# PCA9685.net
KiCad netlist of a schematic drawn in Altium Designer
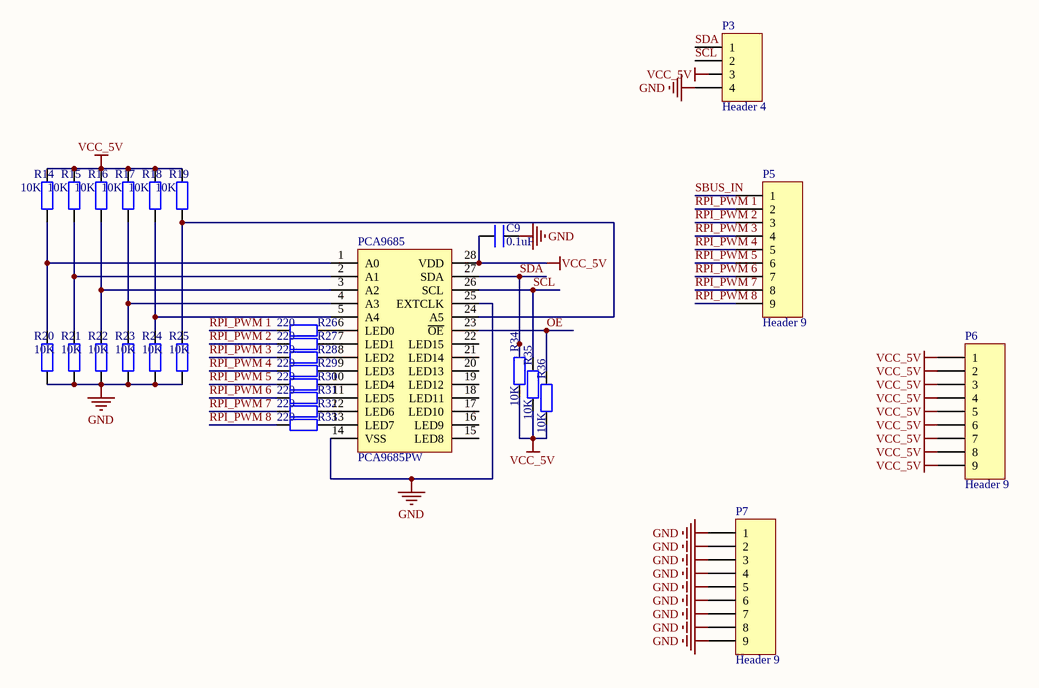
[diagram p0: PCA9685.SchDoc]

(export (version "E")
  (design (tool "Eeschema 10.0.6"))
  (components
    (comp (ref "C9") (value "0.1uF") (footprint "0805") (libsource (lib "OLED模块封装库") (part "C")))
    (comp (ref "P3")
      (value "Header 4")
      (footprint "HDR1X4")
      (description "Header, 4-Pin")
      (fields (field (name "PUBLISHER") "Altium Limited"))
      (libsource (lib "Miscellaneous Connectors") (part "Header 4"))
    )
    (comp (ref "P5")
      (value "Header 9")
      (footprint "HDR1X9")
      (description "Header, 9-Pin")
      (fields (field (name "PUBLISHER") "Altium Limited"))
      (libsource (lib "Miscellaneous Connectors") (part "Header 9"))
    )
    (comp (ref "P6")
      (value "Header 9")
      (footprint "HDR1X9")
      (description "Header, 9-Pin")
      (fields (field (name "PUBLISHER") "Altium Limited"))
      (libsource (lib "Miscellaneous Connectors") (part "Header 9"))
    )
    (comp (ref "P7")
      (value "Header 9")
      (footprint "HDR1X9")
      (description "Header, 9-Pin")
      (fields (field (name "PUBLISHER") "Altium Limited"))
      (libsource (lib "Miscellaneous Connectors") (part "Header 9"))
    )
    (comp (ref "PCA9685")
      (value "PCA9685PW")
      (footprint "PCA9685PW")
      (libsource (lib "Integrated_PCA 9685") (part "PCA9685PW"))
    )
    (comp (ref "R14")
      (value "10K")
      (footprint "3.5TFTLCD封装库:0805")
      (description "Resistor")
      (fields (field (name "Comment") "Res2") (field (name "PUBLISHER") "Altium Limited"))
      (libsource (lib "") (part "Res2_1"))
    )
    (comp (ref "R15")
      (value "10K")
      (footprint "3.5TFTLCD封装库:0805")
      (description "Resistor")
      (fields (field (name "Comment") "Res2") (field (name "PUBLISHER") "Altium Limited"))
      (libsource (lib "") (part "Res2_1"))
    )
    (comp (ref "R16")
      (value "10K")
      (footprint "3.5TFTLCD封装库:0805")
      (description "Resistor")
      (fields (field (name "Comment") "Res2") (field (name "PUBLISHER") "Altium Limited"))
      (libsource (lib "") (part "Res2_1"))
    )
    (comp (ref "R17")
      (value "10K")
      (footprint "3.5TFTLCD封装库:0805")
      (description "Resistor")
      (fields (field (name "Comment") "Res2") (field (name "PUBLISHER") "Altium Limited"))
      (libsource (lib "") (part "Res2_1"))
    )
    (comp (ref "R18")
      (value "10K")
      (footprint "3.5TFTLCD封装库:0805")
      (description "Resistor")
      (fields (field (name "Comment") "Res2") (field (name "PUBLISHER") "Altium Limited"))
      (libsource (lib "") (part "Res2_1"))
    )
    (comp (ref "R19")
      (value "10K")
      (footprint "3.5TFTLCD封装库:0805")
      (description "Resistor")
      (fields (field (name "Comment") "Res2") (field (name "PUBLISHER") "Altium Limited"))
      (libsource (lib "") (part "Res2_1"))
    )
    (comp (ref "R20")
      (value "10K")
      (footprint "3.5TFTLCD封装库:0805")
      (description "Resistor")
      (fields (field (name "Comment") "Res2") (field (name "PUBLISHER") "Altium Limited"))
      (libsource (lib "") (part "Res2_1"))
    )
    (comp (ref "R21")
      (value "10K")
      (footprint "3.5TFTLCD封装库:0805")
      (description "Resistor")
      (fields (field (name "Comment") "Res2") (field (name "PUBLISHER") "Altium Limited"))
      (libsource (lib "") (part "Res2_1"))
    )
    (comp (ref "R22")
      (value "10K")
      (footprint "3.5TFTLCD封装库:0805")
      (description "Resistor")
      (fields (field (name "Comment") "Res2") (field (name "PUBLISHER") "Altium Limited"))
      (libsource (lib "") (part "Res2_1"))
    )
    (comp (ref "R23")
      (value "10K")
      (footprint "3.5TFTLCD封装库:0805")
      (description "Resistor")
      (fields (field (name "Comment") "Res2") (field (name "PUBLISHER") "Altium Limited"))
      (libsource (lib "") (part "Res2_1"))
    )
    (comp (ref "R24")
      (value "10K")
      (footprint "3.5TFTLCD封装库:0805")
      (description "Resistor")
      (fields (field (name "Comment") "Res2") (field (name "PUBLISHER") "Altium Limited"))
      (libsource (lib "") (part "Res2_1"))
    )
    (comp (ref "R25")
      (value "10K")
      (footprint "3.5TFTLCD封装库:0805")
      (description "Resistor")
      (fields (field (name "Comment") "Res2") (field (name "PUBLISHER") "Altium Limited"))
      (libsource (lib "") (part "Res2_1"))
    )
    (comp (ref "R26")
      (value "220")
      (footprint "3.5TFTLCD封装库:0805")
      (description "Resistor")
      (fields (field (name "Comment") "Res2") (field (name "PUBLISHER") "Altium Limited"))
      (libsource (lib "Miscellaneous Devices") (part "Res2"))
    )
    (comp (ref "R27")
      (value "220")
      (footprint "3.5TFTLCD封装库:0805")
      (description "Resistor")
      (fields (field (name "Comment") "Res2") (field (name "PUBLISHER") "Altium Limited"))
      (libsource (lib "Miscellaneous Devices") (part "Res2"))
    )
    (comp (ref "R28")
      (value "220")
      (footprint "3.5TFTLCD封装库:0805")
      (description "Resistor")
      (fields (field (name "Comment") "Res2") (field (name "PUBLISHER") "Altium Limited"))
      (libsource (lib "Miscellaneous Devices") (part "Res2"))
    )
    (comp (ref "R29")
      (value "220")
      (footprint "3.5TFTLCD封装库:0805")
      (description "Resistor")
      (fields (field (name "Comment") "Res2") (field (name "PUBLISHER") "Altium Limited"))
      (libsource (lib "Miscellaneous Devices") (part "Res2"))
    )
    (comp (ref "R30")
      (value "220")
      (footprint "3.5TFTLCD封装库:0805")
      (description "Resistor")
      (fields (field (name "Comment") "Res2") (field (name "PUBLISHER") "Altium Limited"))
      (libsource (lib "Miscellaneous Devices") (part "Res2"))
    )
    (comp (ref "R31")
      (value "220")
      (footprint "3.5TFTLCD封装库:0805")
      (description "Resistor")
      (fields (field (name "Comment") "Res2") (field (name "PUBLISHER") "Altium Limited"))
      (libsource (lib "Miscellaneous Devices") (part "Res2"))
    )
    (comp (ref "R32")
      (value "220")
      (footprint "3.5TFTLCD封装库:0805")
      (description "Resistor")
      (fields (field (name "Comment") "Res2") (field (name "PUBLISHER") "Altium Limited"))
      (libsource (lib "Miscellaneous Devices") (part "Res2"))
    )
    (comp (ref "R33")
      (value "220")
      (footprint "3.5TFTLCD封装库:0805")
      (description "Resistor")
      (fields (field (name "Comment") "Res2") (field (name "PUBLISHER") "Altium Limited"))
      (libsource (lib "Miscellaneous Devices") (part "Res2"))
    )
    (comp (ref "R34")
      (value "10K")
      (footprint "3.5TFTLCD封装库:0805")
      (description "Resistor")
      (fields (field (name "Comment") "Res2") (field (name "PUBLISHER") "Altium Limited"))
      (libsource (lib "") (part "Res2_1"))
    )
    (comp (ref "R35")
      (value "10K")
      (footprint "3.5TFTLCD封装库:0805")
      (description "Resistor")
      (fields (field (name "Comment") "Res2") (field (name "PUBLISHER") "Altium Limited"))
      (libsource (lib "") (part "Res2_1"))
    )
    (comp (ref "R36")
      (value "10K")
      (footprint "3.5TFTLCD封装库:0805")
      (description "Resistor")
      (fields (field (name "Comment") "Res2") (field (name "PUBLISHER") "Altium Limited"))
      (libsource (lib "") (part "Res2_1"))
    )
  )
  (nets
    (net (code "1") (name "/OE") (class "Default")
      (node (ref "PCA9685") (pin "23") (pinfunction "~{OE}_23") (pintype "passive"))
      (node (ref "R36") (pin "1") (pinfunction "1_1") (pintype "passive"))
    )
    (net (code "2") (name "/RPI_PWM 1") (class "Default")
      (node (ref "P5") (pin "2") (pinfunction "2_2") (pintype "passive"))
      (node (ref "R26") (pin "1") (pinfunction "1_1") (pintype "passive"))
    )
    (net (code "3") (name "/RPI_PWM 2") (class "Default")
      (node (ref "P5") (pin "3") (pinfunction "3_3") (pintype "passive"))
      (node (ref "R27") (pin "1") (pinfunction "1_1") (pintype "passive"))
    )
    (net (code "4") (name "/RPI_PWM 3") (class "Default")
      (node (ref "P5") (pin "4") (pinfunction "4_4") (pintype "passive"))
      (node (ref "R28") (pin "1") (pinfunction "1_1") (pintype "passive"))
    )
    (net (code "5") (name "/RPI_PWM 4") (class "Default")
      (node (ref "P5") (pin "5") (pinfunction "5_5") (pintype "passive"))
      (node (ref "R29") (pin "1") (pinfunction "1_1") (pintype "passive"))
    )
    (net (code "6") (name "/RPI_PWM 5") (class "Default")
      (node (ref "P5") (pin "6") (pinfunction "6_6") (pintype "passive"))
      (node (ref "R30") (pin "1") (pinfunction "1_1") (pintype "passive"))
    )
    (net (code "7") (name "/RPI_PWM 6") (class "Default")
      (node (ref "P5") (pin "7") (pinfunction "7_7") (pintype "passive"))
      (node (ref "R31") (pin "1") (pinfunction "1_1") (pintype "passive"))
    )
    (net (code "8") (name "/RPI_PWM 7") (class "Default")
      (node (ref "P5") (pin "8") (pinfunction "8_8") (pintype "passive"))
      (node (ref "R32") (pin "1") (pinfunction "1_1") (pintype "passive"))
    )
    (net (code "9") (name "/RPI_PWM 8") (class "Default")
      (node (ref "P5") (pin "9") (pinfunction "9_9") (pintype "passive"))
      (node (ref "R33") (pin "1") (pinfunction "1_1") (pintype "passive"))
    )
    (net (code "10") (name "/SBUS_IN") (class "Default")
      (node (ref "P5") (pin "1") (pinfunction "1_1") (pintype "passive"))
    )
    (net (code "11") (name "/SCL") (class "Default")
      (node (ref "P3") (pin "2") (pinfunction "2_2") (pintype "passive"))
      (node (ref "PCA9685") (pin "26") (pinfunction "SCL_26") (pintype "passive"))
      (node (ref "R35") (pin "1") (pinfunction "1_1") (pintype "passive"))
    )
    (net (code "12") (name "/SDA") (class "Default")
      (node (ref "P3") (pin "1") (pinfunction "1_1") (pintype "passive"))
      (node (ref "PCA9685") (pin "27") (pinfunction "SDA_27") (pintype "passive"))
      (node (ref "R34") (pin "1") (pinfunction "1_1") (pintype "passive"))
    )
    (net (code "13") (name "GND") (class "Default")
      (node (ref "C9") (pin "2") (pintype "passive"))
      (node (ref "P3") (pin "4") (pinfunction "4_4") (pintype "passive"))
      (node (ref "P7") (pin "1") (pinfunction "1_1") (pintype "passive"))
      (node (ref "P7") (pin "2") (pinfunction "2_2") (pintype "passive"))
      (node (ref "P7") (pin "3") (pinfunction "3_3") (pintype "passive"))
      (node (ref "P7") (pin "4") (pinfunction "4_4") (pintype "passive"))
      (node (ref "P7") (pin "5") (pinfunction "5_5") (pintype "passive"))
      (node (ref "P7") (pin "6") (pinfunction "6_6") (pintype "passive"))
      (node (ref "P7") (pin "7") (pinfunction "7_7") (pintype "passive"))
      (node (ref "P7") (pin "8") (pinfunction "8_8") (pintype "passive"))
      (node (ref "P7") (pin "9") (pinfunction "9_9") (pintype "passive"))
      (node (ref "PCA9685") (pin "14") (pinfunction "VSS_14") (pintype "passive"))
      (node (ref "PCA9685") (pin "25") (pinfunction "EXTCLK_25") (pintype "passive"))
      (node (ref "R20") (pin "2") (pinfunction "2_2") (pintype "passive"))
      (node (ref "R21") (pin "2") (pinfunction "2_2") (pintype "passive"))
      (node (ref "R22") (pin "2") (pinfunction "2_2") (pintype "passive"))
      (node (ref "R23") (pin "2") (pinfunction "2_2") (pintype "passive"))
      (node (ref "R24") (pin "2") (pinfunction "2_2") (pintype "passive"))
      (node (ref "R25") (pin "2") (pinfunction "2_2") (pintype "passive"))
    )
    (net (code "14") (name "Net-(PCA9685-A0)") (class "Default")
      (node (ref "PCA9685") (pin "1") (pinfunction "A0_1") (pintype "passive"))
      (node (ref "R14") (pin "2") (pinfunction "2_2") (pintype "passive"))
      (node (ref "R20") (pin "1") (pinfunction "1_1") (pintype "passive"))
    )
    (net (code "15") (name "Net-(PCA9685-A1)") (class "Default")
      (node (ref "PCA9685") (pin "2") (pinfunction "A1_2") (pintype "passive"))
      (node (ref "R15") (pin "2") (pinfunction "2_2") (pintype "passive"))
      (node (ref "R21") (pin "1") (pinfunction "1_1") (pintype "passive"))
    )
    (net (code "16") (name "Net-(PCA9685-A2)") (class "Default")
      (node (ref "PCA9685") (pin "3") (pinfunction "A2_3") (pintype "passive"))
      (node (ref "R16") (pin "2") (pinfunction "2_2") (pintype "passive"))
      (node (ref "R22") (pin "1") (pinfunction "1_1") (pintype "passive"))
    )
    (net (code "17") (name "Net-(PCA9685-A3)") (class "Default")
      (node (ref "PCA9685") (pin "4") (pinfunction "A3_4") (pintype "passive"))
      (node (ref "R17") (pin "2") (pinfunction "2_2") (pintype "passive"))
      (node (ref "R23") (pin "1") (pinfunction "1_1") (pintype "passive"))
    )
    (net (code "18") (name "Net-(PCA9685-A4)") (class "Default")
      (node (ref "PCA9685") (pin "5") (pinfunction "A4_5") (pintype "passive"))
      (node (ref "R18") (pin "2") (pinfunction "2_2") (pintype "passive"))
      (node (ref "R24") (pin "1") (pinfunction "1_1") (pintype "passive"))
    )
    (net (code "19") (name "Net-(PCA9685-A5)") (class "Default")
      (node (ref "PCA9685") (pin "24") (pinfunction "A5_24") (pintype "passive"))
      (node (ref "R19") (pin "2") (pinfunction "2_2") (pintype "passive"))
      (node (ref "R25") (pin "1") (pinfunction "1_1") (pintype "passive"))
    )
    (net (code "20") (name "Net-(PCA9685-LED0)") (class "Default")
      (node (ref "PCA9685") (pin "6") (pinfunction "LED0_6") (pintype "passive"))
      (node (ref "R26") (pin "2") (pinfunction "2_2") (pintype "passive"))
    )
    (net (code "21") (name "Net-(PCA9685-LED1)") (class "Default")
      (node (ref "PCA9685") (pin "7") (pinfunction "LED1_7") (pintype "passive"))
      (node (ref "R27") (pin "2") (pinfunction "2_2") (pintype "passive"))
    )
    (net (code "22") (name "Net-(PCA9685-LED2)") (class "Default")
      (node (ref "PCA9685") (pin "8") (pinfunction "LED2_8") (pintype "passive"))
      (node (ref "R28") (pin "2") (pinfunction "2_2") (pintype "passive"))
    )
    (net (code "23") (name "Net-(PCA9685-LED3)") (class "Default")
      (node (ref "PCA9685") (pin "9") (pinfunction "LED3_9") (pintype "passive"))
      (node (ref "R29") (pin "2") (pinfunction "2_2") (pintype "passive"))
    )
    (net (code "24") (name "Net-(PCA9685-LED4)") (class "Default")
      (node (ref "PCA9685") (pin "10") (pinfunction "LED4_10") (pintype "passive"))
      (node (ref "R30") (pin "2") (pinfunction "2_2") (pintype "passive"))
    )
    (net (code "25") (name "Net-(PCA9685-LED5)") (class "Default")
      (node (ref "PCA9685") (pin "11") (pinfunction "LED5_11") (pintype "passive"))
      (node (ref "R31") (pin "2") (pinfunction "2_2") (pintype "passive"))
    )
    (net (code "26") (name "Net-(PCA9685-LED6)") (class "Default")
      (node (ref "PCA9685") (pin "12") (pinfunction "LED6_12") (pintype "passive"))
      (node (ref "R32") (pin "2") (pinfunction "2_2") (pintype "passive"))
    )
    (net (code "27") (name "Net-(PCA9685-LED7)") (class "Default")
      (node (ref "PCA9685") (pin "13") (pinfunction "LED7_13") (pintype "passive"))
      (node (ref "R33") (pin "2") (pinfunction "2_2") (pintype "passive"))
    )
    (net (code "28") (name "VCC_5V") (class "Default")
      (node (ref "C9") (pin "1") (pintype "passive"))
      (node (ref "P6") (pin "1") (pinfunction "1_1") (pintype "passive"))
      (node (ref "P6") (pin "2") (pinfunction "2_2") (pintype "passive"))
      (node (ref "P6") (pin "3") (pinfunction "3_3") (pintype "passive"))
      (node (ref "P6") (pin "4") (pinfunction "4_4") (pintype "passive"))
      (node (ref "P6") (pin "5") (pinfunction "5_5") (pintype "passive"))
      (node (ref "P6") (pin "6") (pinfunction "6_6") (pintype "passive"))
      (node (ref "P6") (pin "7") (pinfunction "7_7") (pintype "passive"))
      (node (ref "P6") (pin "8") (pinfunction "8_8") (pintype "passive"))
      (node (ref "P6") (pin "9") (pinfunction "9_9") (pintype "passive"))
      (node (ref "PCA9685") (pin "28") (pinfunction "VDD_28") (pintype "passive"))
      (node (ref "R14") (pin "1") (pinfunction "1_1") (pintype "passive"))
      (node (ref "R15") (pin "1") (pinfunction "1_1") (pintype "passive"))
      (node (ref "R16") (pin "1") (pinfunction "1_1") (pintype "passive"))
      (node (ref "R17") (pin "1") (pinfunction "1_1") (pintype "passive"))
      (node (ref "R18") (pin "1") (pinfunction "1_1") (pintype "passive"))
      (node (ref "R19") (pin "1") (pinfunction "1_1") (pintype "passive"))
      (node (ref "R34") (pin "2") (pinfunction "2_2") (pintype "passive"))
      (node (ref "R35") (pin "2") (pinfunction "2_2") (pintype "passive"))
      (node (ref "R36") (pin "2") (pinfunction "2_2") (pintype "passive"))
    )
    (net (code "29") (name "unconnected-(P3-Pad3)") (class "Default")
      (node (ref "P3") (pin "3") (pinfunction "3_3") (pintype "passive"))
    )
    (net (code "30") (name "unconnected-(PCA9685-LED8-Pad15)") (class "Default")
      (node (ref "PCA9685") (pin "15") (pinfunction "LED8_15") (pintype "passive"))
    )
    (net (code "31") (name "unconnected-(PCA9685-LED9-Pad16)") (class "Default")
      (node (ref "PCA9685") (pin "16") (pinfunction "LED9_16") (pintype "passive"))
    )
    (net (code "32") (name "unconnected-(PCA9685-LED10-Pad17)") (class "Default")
      (node (ref "PCA9685") (pin "17") (pinfunction "LED10_17") (pintype "passive"))
    )
    (net (code "33") (name "unconnected-(PCA9685-LED11-Pad18)") (class "Default")
      (node (ref "PCA9685") (pin "18") (pinfunction "LED11_18") (pintype "passive"))
    )
    (net (code "34") (name "unconnected-(PCA9685-LED12-Pad19)") (class "Default")
      (node (ref "PCA9685") (pin "19") (pinfunction "LED12_19") (pintype "passive"))
    )
    (net (code "35") (name "unconnected-(PCA9685-LED13-Pad20)") (class "Default")
      (node (ref "PCA9685") (pin "20") (pinfunction "LED13_20") (pintype "passive"))
    )
    (net (code "36") (name "unconnected-(PCA9685-LED14-Pad21)") (class "Default")
      (node (ref "PCA9685") (pin "21") (pinfunction "LED14_21") (pintype "passive"))
    )
    (net (code "37") (name "unconnected-(PCA9685-LED15-Pad22)") (class "Default")
      (node (ref "PCA9685") (pin "22") (pinfunction "LED15_22") (pintype "passive"))
    )
  )
)
